# RHD2164_USBC.net
KiCad netlist of a schematic drawn in Altium Designer
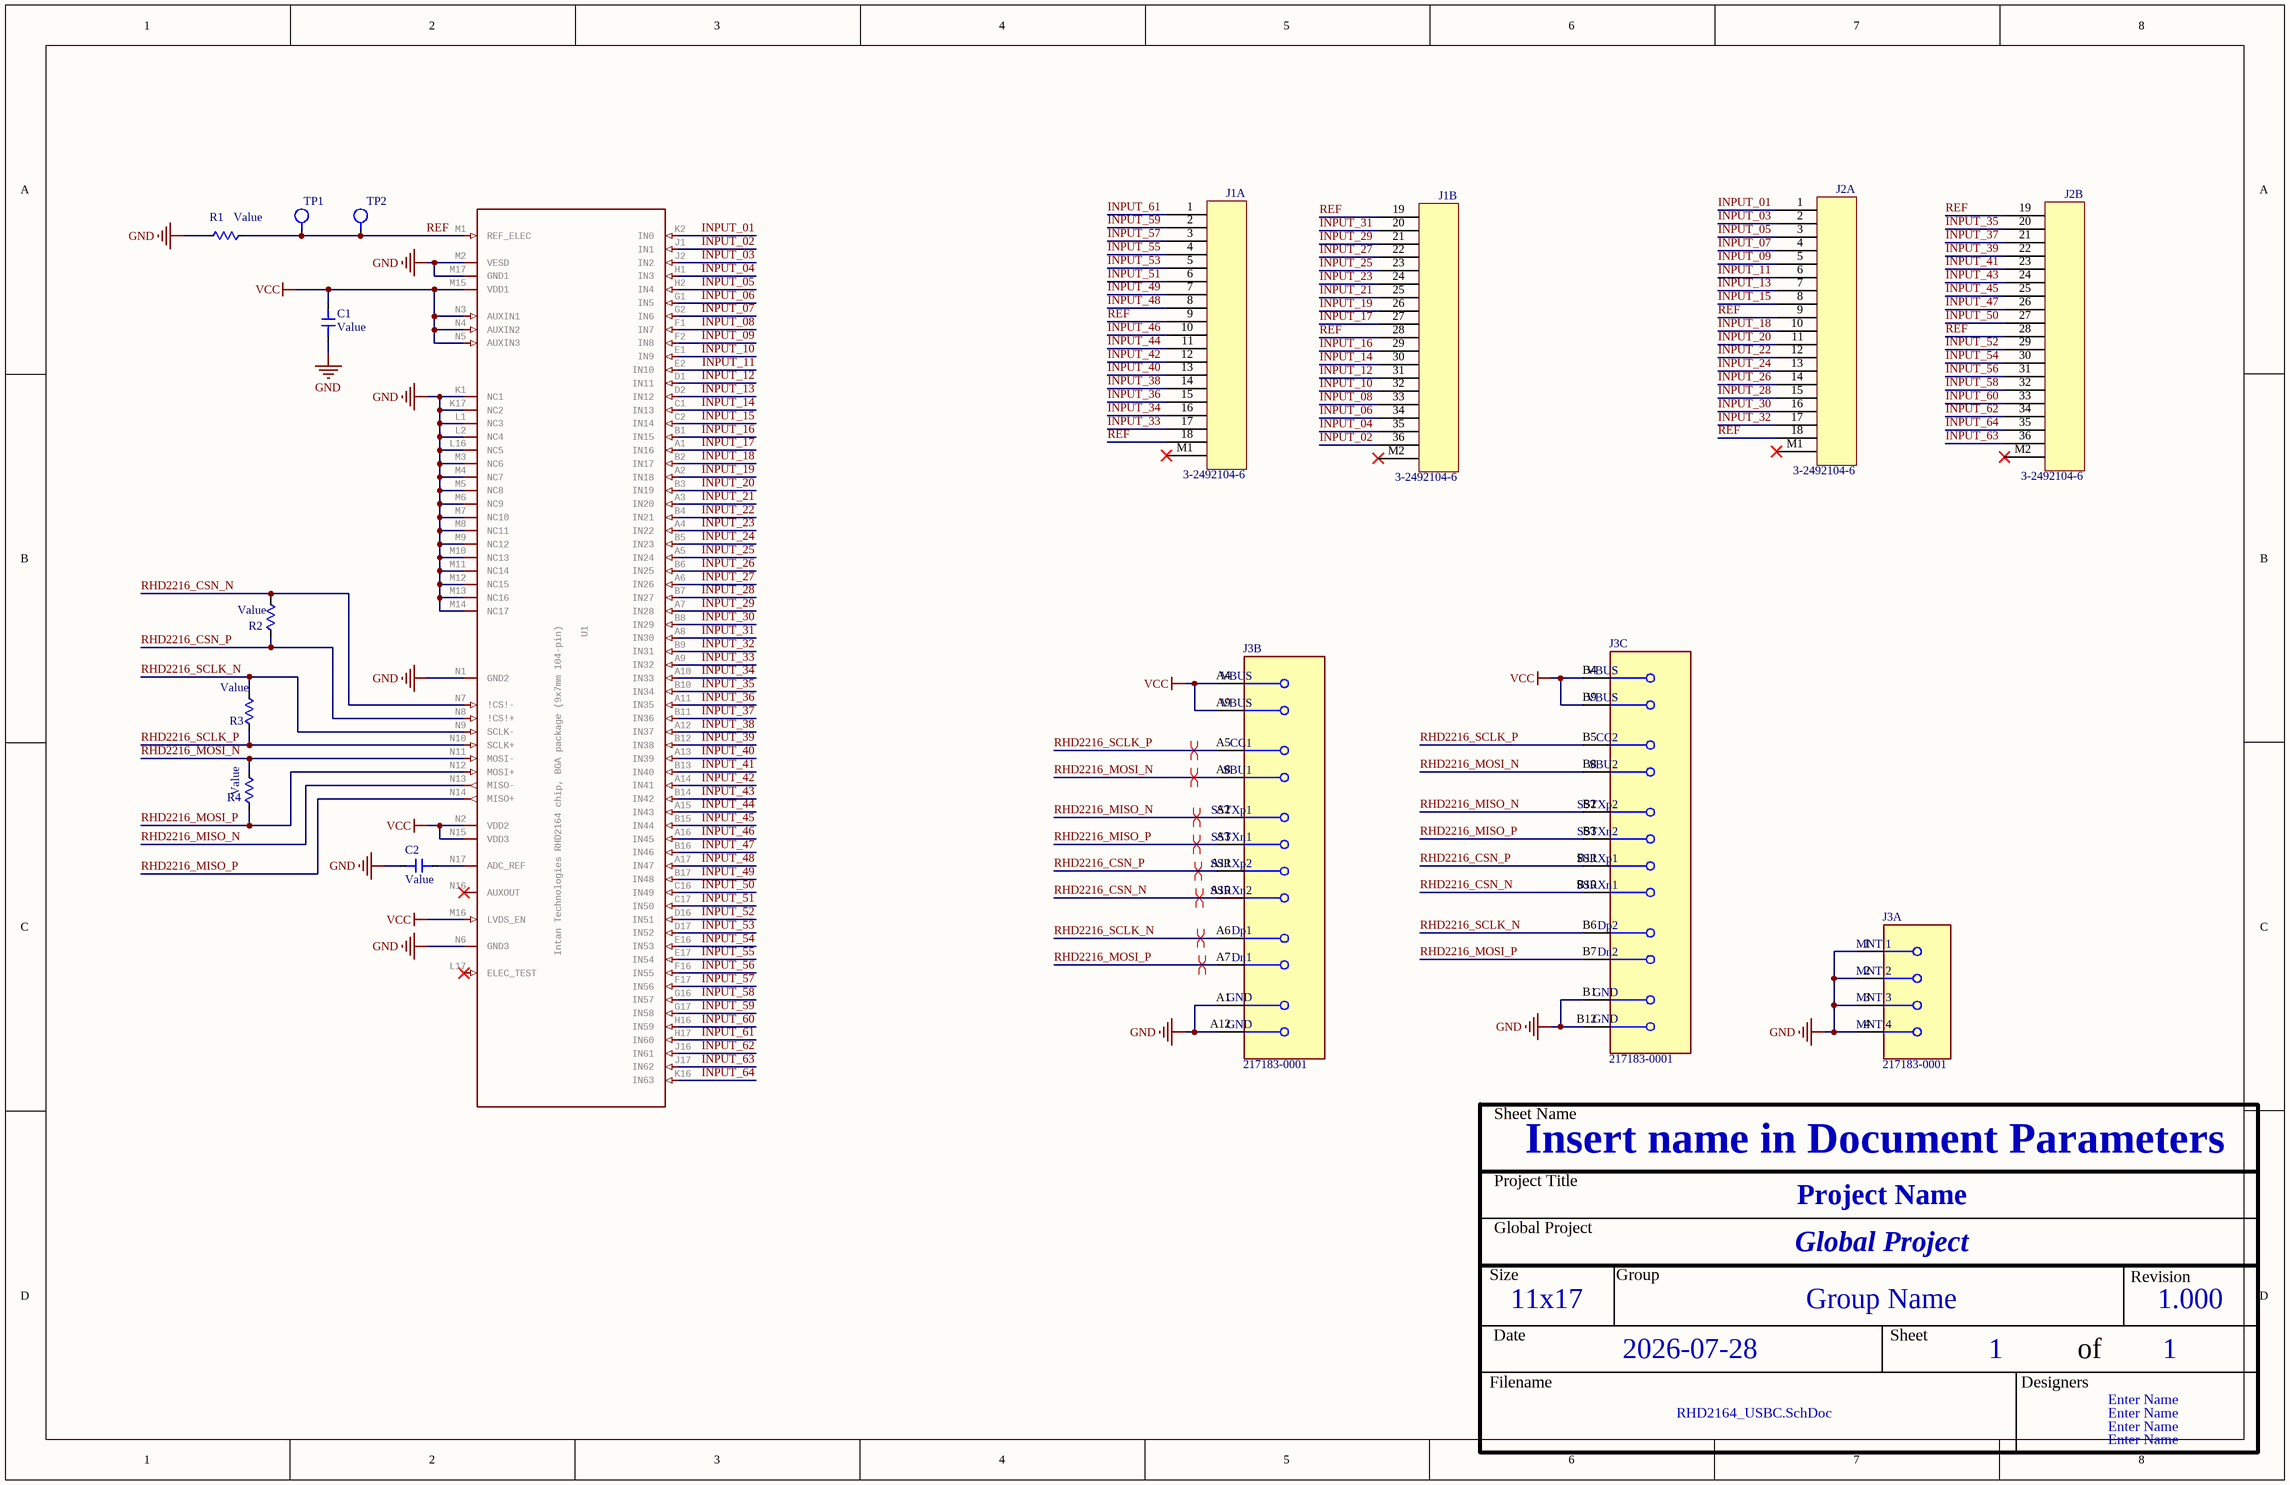
[diagram p0: RHD2164_USBC.SchDoc]

(export (version "E")
  (design (tool "Eeschema 10.0.6"))
  (components
    (comp (ref "C1")
      (value "Value")
      (footprint "0402_CAPACITOR")
      (description "Capacitor")
      (libsource (lib "RHD2164_USBC_V2") (part "Capacitor"))
    )
    (comp (ref "C2")
      (value "Value")
      (footprint "0402_CAPACITOR")
      (description "Capacitor")
      (libsource (lib "RHD2164_USBC_V2") (part "Capacitor"))
    )
    (comp (ref "J1")
      (value "3-2492104-6")
      (footprint "CON_ZIF_RA_36POS")
      (description "36 Position FPC Connector Contacts, Bottom 0.020\" (0.50mm) Surface Mount, Right Angle")
      (libsource (lib "RHD2164_USBC_V2") (part "CON_ZIF_RA_36POS"))
    )
    (comp (ref "J2")
      (value "3-2492104-6")
      (footprint "CON_ZIF_RA_36POS")
      (description "36 Position FPC Connector Contacts, Bottom 0.020\" (0.50mm) Surface Mount, Right Angle")
      (libsource (lib "RHD2164_USBC_V2") (part "CON_ZIF_RA_36POS"))
    )
    (comp (ref "J3")
      (value "217183-0001")
      (footprint "FP-217183-0001-MFG")
      (libsource (lib "Connectors") (part "CON_USBC_TH_SMT"))
    )
    (comp (ref "R1")
      (value "Value")
      (footprint "0402_Resistor")
      (description "Resistor")
      (libsource (lib "RHD2164_USBC_V2") (part "Resistor"))
    )
    (comp (ref "R2")
      (value "Value")
      (footprint "0402_Resistor")
      (description "Resistor")
      (libsource (lib "RHD2164_USBC_V2") (part "Resistor"))
    )
    (comp (ref "R3")
      (value "Value")
      (footprint "0402_Resistor")
      (description "Resistor")
      (libsource (lib "RHD2164_USBC_V2") (part "Resistor"))
    )
    (comp (ref "R4")
      (value "Value")
      (footprint "0402_Resistor")
      (description "Resistor")
      (libsource (lib "RHD2164_USBC_V2") (part "Resistor"))
    )
    (comp (ref "TP1")
      (value "TP_Small")
      (footprint "TP_Small_M2")
      (libsource (lib "RHD2164_USBC_V2") (part "TP_Small"))
    )
    (comp (ref "TP2")
      (value "TP_Small")
      (footprint "TP_Small_M2")
      (libsource (lib "RHD2164_USBC_V2") (part "TP_Small"))
    )
    (comp (ref "U1")
      (value "Intan Technologies RHD2164 chip, BGA package (9x7mm 104-pin)")
      (footprint "RHD2164_BGA")
      (libsource (lib "RHD2164_USBC_V2") (part "RHD2164_BGA_BGA"))
    )
  )
  (nets
    (net (code "1") (name "/INPUT_01") (class "Default")
      (node (ref "J2") (pin "1") (pinfunction "1_1") (pintype "passive"))
      (node (ref "U1") (pin "K2") (pinfunction "IN0_K2") (pintype "input"))
    )
    (net (code "2") (name "/INPUT_02") (class "Default")
      (node (ref "J1") (pin "36") (pinfunction "36_36") (pintype "passive"))
      (node (ref "U1") (pin "J1") (pinfunction "IN1_J1") (pintype "input"))
    )
    (net (code "3") (name "/INPUT_03") (class "Default")
      (node (ref "J2") (pin "2") (pinfunction "2_2") (pintype "passive"))
      (node (ref "U1") (pin "J2") (pinfunction "IN2_J2") (pintype "input"))
    )
    (net (code "4") (name "/INPUT_04") (class "Default")
      (node (ref "J1") (pin "35") (pinfunction "35_35") (pintype "passive"))
      (node (ref "U1") (pin "H1") (pinfunction "IN3_H1") (pintype "input"))
    )
    (net (code "5") (name "/INPUT_05") (class "Default")
      (node (ref "J2") (pin "3") (pinfunction "3_3") (pintype "passive"))
      (node (ref "U1") (pin "H2") (pinfunction "IN4_H2") (pintype "input"))
    )
    (net (code "6") (name "/INPUT_06") (class "Default")
      (node (ref "J1") (pin "34") (pinfunction "34_34") (pintype "passive"))
      (node (ref "U1") (pin "G1") (pinfunction "IN5_G1") (pintype "input"))
    )
    (net (code "7") (name "/INPUT_07") (class "Default")
      (node (ref "J2") (pin "4") (pinfunction "4_4") (pintype "passive"))
      (node (ref "U1") (pin "G2") (pinfunction "IN6_G2") (pintype "input"))
    )
    (net (code "8") (name "/INPUT_08") (class "Default")
      (node (ref "J1") (pin "33") (pinfunction "33_33") (pintype "passive"))
      (node (ref "U1") (pin "F1") (pinfunction "IN7_F1") (pintype "input"))
    )
    (net (code "9") (name "/INPUT_09") (class "Default")
      (node (ref "J2") (pin "5") (pinfunction "5_5") (pintype "passive"))
      (node (ref "U1") (pin "F2") (pinfunction "IN8_F2") (pintype "input"))
    )
    (net (code "10") (name "/INPUT_10") (class "Default")
      (node (ref "J1") (pin "32") (pinfunction "32_32") (pintype "passive"))
      (node (ref "U1") (pin "E1") (pinfunction "IN9_E1") (pintype "input"))
    )
    (net (code "11") (name "/INPUT_11") (class "Default")
      (node (ref "J2") (pin "6") (pinfunction "6_6") (pintype "passive"))
      (node (ref "U1") (pin "E2") (pinfunction "IN10_E2") (pintype "input"))
    )
    (net (code "12") (name "/INPUT_12") (class "Default")
      (node (ref "J1") (pin "31") (pinfunction "31_31") (pintype "passive"))
      (node (ref "U1") (pin "D1") (pinfunction "IN11_D1") (pintype "input"))
    )
    (net (code "13") (name "/INPUT_13") (class "Default")
      (node (ref "J2") (pin "7") (pinfunction "7_7") (pintype "passive"))
      (node (ref "U1") (pin "D2") (pinfunction "IN12_D2") (pintype "input"))
    )
    (net (code "14") (name "/INPUT_14") (class "Default")
      (node (ref "J1") (pin "30") (pinfunction "30_30") (pintype "passive"))
      (node (ref "U1") (pin "C1") (pinfunction "IN13_C1") (pintype "input"))
    )
    (net (code "15") (name "/INPUT_15") (class "Default")
      (node (ref "J2") (pin "8") (pinfunction "8_8") (pintype "passive"))
      (node (ref "U1") (pin "C2") (pinfunction "IN14_C2") (pintype "input"))
    )
    (net (code "16") (name "/INPUT_16") (class "Default")
      (node (ref "J1") (pin "29") (pinfunction "29_29") (pintype "passive"))
      (node (ref "U1") (pin "B1") (pinfunction "IN15_B1") (pintype "input"))
    )
    (net (code "17") (name "/INPUT_17") (class "Default")
      (node (ref "J1") (pin "27") (pinfunction "27_27") (pintype "passive"))
      (node (ref "U1") (pin "A1") (pinfunction "IN16_A1") (pintype "input"))
    )
    (net (code "18") (name "/INPUT_18") (class "Default")
      (node (ref "J2") (pin "10") (pinfunction "10_10") (pintype "passive"))
      (node (ref "U1") (pin "B2") (pinfunction "IN17_B2") (pintype "input"))
    )
    (net (code "19") (name "/INPUT_19") (class "Default")
      (node (ref "J1") (pin "26") (pinfunction "26_26") (pintype "passive"))
      (node (ref "U1") (pin "A2") (pinfunction "IN18_A2") (pintype "input"))
    )
    (net (code "20") (name "/INPUT_20") (class "Default")
      (node (ref "J2") (pin "11") (pinfunction "11_11") (pintype "passive"))
      (node (ref "U1") (pin "B3") (pinfunction "IN19_B3") (pintype "input"))
    )
    (net (code "21") (name "/INPUT_21") (class "Default")
      (node (ref "J1") (pin "25") (pinfunction "25_25") (pintype "passive"))
      (node (ref "U1") (pin "A3") (pinfunction "IN20_A3") (pintype "input"))
    )
    (net (code "22") (name "/INPUT_22") (class "Default")
      (node (ref "J2") (pin "12") (pinfunction "12_12") (pintype "passive"))
      (node (ref "U1") (pin "B4") (pinfunction "IN21_B4") (pintype "input"))
    )
    (net (code "23") (name "/INPUT_23") (class "Default")
      (node (ref "J1") (pin "24") (pinfunction "24_24") (pintype "passive"))
      (node (ref "U1") (pin "A4") (pinfunction "IN22_A4") (pintype "input"))
    )
    (net (code "24") (name "/INPUT_24") (class "Default")
      (node (ref "J2") (pin "13") (pinfunction "13_13") (pintype "passive"))
      (node (ref "U1") (pin "B5") (pinfunction "IN23_B5") (pintype "input"))
    )
    (net (code "25") (name "/INPUT_25") (class "Default")
      (node (ref "J1") (pin "23") (pinfunction "23_23") (pintype "passive"))
      (node (ref "U1") (pin "A5") (pinfunction "IN24_A5") (pintype "input"))
    )
    (net (code "26") (name "/INPUT_26") (class "Default")
      (node (ref "J2") (pin "14") (pinfunction "14_14") (pintype "passive"))
      (node (ref "U1") (pin "B6") (pinfunction "IN25_B6") (pintype "input"))
    )
    (net (code "27") (name "/INPUT_27") (class "Default")
      (node (ref "J1") (pin "22") (pinfunction "22_22") (pintype "passive"))
      (node (ref "U1") (pin "A6") (pinfunction "IN26_A6") (pintype "input"))
    )
    (net (code "28") (name "/INPUT_28") (class "Default")
      (node (ref "J2") (pin "15") (pinfunction "15_15") (pintype "passive"))
      (node (ref "U1") (pin "B7") (pinfunction "IN27_B7") (pintype "input"))
    )
    (net (code "29") (name "/INPUT_29") (class "Default")
      (node (ref "J1") (pin "21") (pinfunction "21_21") (pintype "passive"))
      (node (ref "U1") (pin "A7") (pinfunction "IN28_A7") (pintype "input"))
    )
    (net (code "30") (name "/INPUT_30") (class "Default")
      (node (ref "J2") (pin "16") (pinfunction "16_16") (pintype "passive"))
      (node (ref "U1") (pin "B8") (pinfunction "IN29_B8") (pintype "input"))
    )
    (net (code "31") (name "/INPUT_31") (class "Default")
      (node (ref "J1") (pin "20") (pinfunction "20_20") (pintype "passive"))
      (node (ref "U1") (pin "A8") (pinfunction "IN30_A8") (pintype "input"))
    )
    (net (code "32") (name "/INPUT_32") (class "Default")
      (node (ref "J2") (pin "17") (pinfunction "17_17") (pintype "passive"))
      (node (ref "U1") (pin "B9") (pinfunction "IN31_B9") (pintype "input"))
    )
    (net (code "33") (name "/INPUT_33") (class "Default")
      (node (ref "J1") (pin "17") (pinfunction "17_17") (pintype "passive"))
      (node (ref "U1") (pin "A9") (pinfunction "IN32_A9") (pintype "input"))
    )
    (net (code "34") (name "/INPUT_34") (class "Default")
      (node (ref "J1") (pin "16") (pinfunction "16_16") (pintype "passive"))
      (node (ref "U1") (pin "A10") (pinfunction "IN33_A10") (pintype "input"))
    )
    (net (code "35") (name "/INPUT_35") (class "Default")
      (node (ref "J2") (pin "20") (pinfunction "20_20") (pintype "passive"))
      (node (ref "U1") (pin "B10") (pinfunction "IN34_B10") (pintype "input"))
    )
    (net (code "36") (name "/INPUT_36") (class "Default")
      (node (ref "J1") (pin "15") (pinfunction "15_15") (pintype "passive"))
      (node (ref "U1") (pin "A11") (pinfunction "IN35_A11") (pintype "input"))
    )
    (net (code "37") (name "/INPUT_37") (class "Default")
      (node (ref "J2") (pin "21") (pinfunction "21_21") (pintype "passive"))
      (node (ref "U1") (pin "B11") (pinfunction "IN36_B11") (pintype "input"))
    )
    (net (code "38") (name "/INPUT_38") (class "Default")
      (node (ref "J1") (pin "14") (pinfunction "14_14") (pintype "passive"))
      (node (ref "U1") (pin "A12") (pinfunction "IN37_A12") (pintype "input"))
    )
    (net (code "39") (name "/INPUT_39") (class "Default")
      (node (ref "J2") (pin "22") (pinfunction "22_22") (pintype "passive"))
      (node (ref "U1") (pin "B12") (pinfunction "IN38_B12") (pintype "input"))
    )
    (net (code "40") (name "/INPUT_40") (class "Default")
      (node (ref "J1") (pin "13") (pinfunction "13_13") (pintype "passive"))
      (node (ref "U1") (pin "A13") (pinfunction "IN39_A13") (pintype "input"))
    )
    (net (code "41") (name "/INPUT_41") (class "Default")
      (node (ref "J2") (pin "23") (pinfunction "23_23") (pintype "passive"))
      (node (ref "U1") (pin "B13") (pinfunction "IN40_B13") (pintype "input"))
    )
    (net (code "42") (name "/INPUT_42") (class "Default")
      (node (ref "J1") (pin "12") (pinfunction "12_12") (pintype "passive"))
      (node (ref "U1") (pin "A14") (pinfunction "IN41_A14") (pintype "input"))
    )
    (net (code "43") (name "/INPUT_43") (class "Default")
      (node (ref "J2") (pin "24") (pinfunction "24_24") (pintype "passive"))
      (node (ref "U1") (pin "B14") (pinfunction "IN42_B14") (pintype "input"))
    )
    (net (code "44") (name "/INPUT_44") (class "Default")
      (node (ref "J1") (pin "11") (pinfunction "11_11") (pintype "passive"))
      (node (ref "U1") (pin "A15") (pinfunction "IN43_A15") (pintype "input"))
    )
    (net (code "45") (name "/INPUT_45") (class "Default")
      (node (ref "J2") (pin "25") (pinfunction "25_25") (pintype "passive"))
      (node (ref "U1") (pin "B15") (pinfunction "IN44_B15") (pintype "input"))
    )
    (net (code "46") (name "/INPUT_46") (class "Default")
      (node (ref "J1") (pin "10") (pinfunction "10_10") (pintype "passive"))
      (node (ref "U1") (pin "A16") (pinfunction "IN45_A16") (pintype "input"))
    )
    (net (code "47") (name "/INPUT_47") (class "Default")
      (node (ref "J2") (pin "26") (pinfunction "26_26") (pintype "passive"))
      (node (ref "U1") (pin "B16") (pinfunction "IN46_B16") (pintype "input"))
    )
    (net (code "48") (name "/INPUT_48") (class "Default")
      (node (ref "J1") (pin "8") (pinfunction "8_8") (pintype "passive"))
      (node (ref "U1") (pin "A17") (pinfunction "IN47_A17") (pintype "input"))
    )
    (net (code "49") (name "/INPUT_49") (class "Default")
      (node (ref "J1") (pin "7") (pinfunction "7_7") (pintype "passive"))
      (node (ref "U1") (pin "B17") (pinfunction "IN48_B17") (pintype "input"))
    )
    (net (code "50") (name "/INPUT_50") (class "Default")
      (node (ref "J2") (pin "27") (pinfunction "27_27") (pintype "passive"))
      (node (ref "U1") (pin "C16") (pinfunction "IN49_C16") (pintype "input"))
    )
    (net (code "51") (name "/INPUT_51") (class "Default")
      (node (ref "J1") (pin "6") (pinfunction "6_6") (pintype "passive"))
      (node (ref "U1") (pin "C17") (pinfunction "IN50_C17") (pintype "input"))
    )
    (net (code "52") (name "/INPUT_52") (class "Default")
      (node (ref "J2") (pin "29") (pinfunction "29_29") (pintype "passive"))
      (node (ref "U1") (pin "D16") (pinfunction "IN51_D16") (pintype "input"))
    )
    (net (code "53") (name "/INPUT_53") (class "Default")
      (node (ref "J1") (pin "5") (pinfunction "5_5") (pintype "passive"))
      (node (ref "U1") (pin "D17") (pinfunction "IN52_D17") (pintype "input"))
    )
    (net (code "54") (name "/INPUT_54") (class "Default")
      (node (ref "J2") (pin "30") (pinfunction "30_30") (pintype "passive"))
      (node (ref "U1") (pin "E16") (pinfunction "IN53_E16") (pintype "input"))
    )
    (net (code "55") (name "/INPUT_55") (class "Default")
      (node (ref "J1") (pin "4") (pinfunction "4_4") (pintype "passive"))
      (node (ref "U1") (pin "E17") (pinfunction "IN54_E17") (pintype "input"))
    )
    (net (code "56") (name "/INPUT_56") (class "Default")
      (node (ref "J2") (pin "31") (pinfunction "31_31") (pintype "passive"))
      (node (ref "U1") (pin "F16") (pinfunction "IN55_F16") (pintype "input"))
    )
    (net (code "57") (name "/INPUT_57") (class "Default")
      (node (ref "J1") (pin "3") (pinfunction "3_3") (pintype "passive"))
      (node (ref "U1") (pin "F17") (pinfunction "IN56_F17") (pintype "input"))
    )
    (net (code "58") (name "/INPUT_58") (class "Default")
      (node (ref "J2") (pin "32") (pinfunction "32_32") (pintype "passive"))
      (node (ref "U1") (pin "G16") (pinfunction "IN57_G16") (pintype "input"))
    )
    (net (code "59") (name "/INPUT_59") (class "Default")
      (node (ref "J1") (pin "2") (pinfunction "2_2") (pintype "passive"))
      (node (ref "U1") (pin "G17") (pinfunction "IN58_G17") (pintype "input"))
    )
    (net (code "60") (name "/INPUT_60") (class "Default")
      (node (ref "J2") (pin "33") (pinfunction "33_33") (pintype "passive"))
      (node (ref "U1") (pin "H16") (pinfunction "IN59_H16") (pintype "input"))
    )
    (net (code "61") (name "/INPUT_61") (class "Default")
      (node (ref "J1") (pin "1") (pinfunction "1_1") (pintype "passive"))
      (node (ref "U1") (pin "H17") (pinfunction "IN60_H17") (pintype "input"))
    )
    (net (code "62") (name "/INPUT_62") (class "Default")
      (node (ref "J2") (pin "34") (pinfunction "34_34") (pintype "passive"))
      (node (ref "U1") (pin "J16") (pinfunction "IN61_J16") (pintype "input"))
    )
    (net (code "63") (name "/INPUT_63") (class "Default")
      (node (ref "J2") (pin "36") (pinfunction "36_36") (pintype "passive"))
      (node (ref "U1") (pin "J17") (pinfunction "IN62_J17") (pintype "input"))
    )
    (net (code "64") (name "/INPUT_64") (class "Default")
      (node (ref "J2") (pin "35") (pinfunction "35_35") (pintype "passive"))
      (node (ref "U1") (pin "K16") (pinfunction "IN63_K16") (pintype "input"))
    )
    (net (code "65") (name "/REF") (class "Default")
      (node (ref "J1") (pin "18") (pinfunction "18_18") (pintype "passive"))
      (node (ref "J1") (pin "19") (pinfunction "19_19") (pintype "passive"))
      (node (ref "J1") (pin "28") (pinfunction "28_28") (pintype "passive"))
      (node (ref "J1") (pin "9") (pinfunction "9_9") (pintype "passive"))
      (node (ref "J2") (pin "18") (pinfunction "18_18") (pintype "passive"))
      (node (ref "J2") (pin "19") (pinfunction "19_19") (pintype "passive"))
      (node (ref "J2") (pin "28") (pinfunction "28_28") (pintype "passive"))
      (node (ref "J2") (pin "9") (pinfunction "9_9") (pintype "passive"))
      (node (ref "R1") (pin "2") (pinfunction "2_2") (pintype "passive"))
      (node (ref "TP1") (pin "1") (pinfunction "1_1") (pintype "passive"))
      (node (ref "TP2") (pin "1") (pinfunction "1_1") (pintype "passive"))
      (node (ref "U1") (pin "M1") (pinfunction "REF_ELEC_M1") (pintype "input"))
    )
    (net (code "66") (name "/RHD2216_CSN_N") (class "Default")
      (node (ref "J3") (pin "A10") (pinfunction "SSRXn2_A10") (pintype "passive"))
      (node (ref "J3") (pin "B10") (pinfunction "SSRXn1_B10") (pintype "passive"))
      (node (ref "R2") (pin "2") (pinfunction "2_2") (pintype "passive"))
      (node (ref "U1") (pin "N7") (pinfunction "!CS!-_N7") (pintype "input"))
    )
    (net (code "67") (name "/RHD2216_CSN_P") (class "Default")
      (node (ref "J3") (pin "A11") (pinfunction "SSRXp2_A11") (pintype "passive"))
      (node (ref "J3") (pin "B11") (pinfunction "SSRXp1_B11") (pintype "passive"))
      (node (ref "R2") (pin "1") (pinfunction "1_1") (pintype "passive"))
      (node (ref "U1") (pin "N8") (pinfunction "!CS!+_N8") (pintype "input"))
    )
    (net (code "68") (name "/RHD2216_MISO_N") (class "Default")
      (node (ref "J3") (pin "A2") (pinfunction "SSTXp1_A2") (pintype "passive"))
      (node (ref "J3") (pin "B2") (pinfunction "SSTXp2_B2") (pintype "passive"))
      (node (ref "U1") (pin "N13") (pinfunction "MISO-_N13") (pintype "output"))
    )
    (net (code "69") (name "/RHD2216_MISO_P") (class "Default")
      (node (ref "J3") (pin "A3") (pinfunction "SSTXn1_A3") (pintype "passive"))
      (node (ref "J3") (pin "B3") (pinfunction "SSTXn2_B3") (pintype "passive"))
      (node (ref "U1") (pin "N14") (pinfunction "MISO+_N14") (pintype "output"))
    )
    (net (code "70") (name "/RHD2216_MOSI_N") (class "Default")
      (node (ref "J3") (pin "A8") (pinfunction "SBU1_A8") (pintype "passive"))
      (node (ref "J3") (pin "B8") (pinfunction "SBU2_B8") (pintype "passive"))
      (node (ref "R4") (pin "2") (pinfunction "2_2") (pintype "passive"))
      (node (ref "U1") (pin "N11") (pinfunction "MOSI-_N11") (pintype "input"))
    )
    (net (code "71") (name "/RHD2216_MOSI_P") (class "Default")
      (node (ref "J3") (pin "A7") (pinfunction "Dn1_A7") (pintype "passive"))
      (node (ref "J3") (pin "B7") (pinfunction "Dn2_B7") (pintype "passive"))
      (node (ref "R4") (pin "1") (pinfunction "1_1") (pintype "passive"))
      (node (ref "U1") (pin "N12") (pinfunction "MOSI+_N12") (pintype "input"))
    )
    (net (code "72") (name "/RHD2216_SCLK_N") (class "Default")
      (node (ref "J3") (pin "A6") (pinfunction "Dp1_A6") (pintype "passive"))
      (node (ref "J3") (pin "B6") (pinfunction "Dp2_B6") (pintype "passive"))
      (node (ref "R3") (pin "2") (pinfunction "2_2") (pintype "passive"))
      (node (ref "U1") (pin "N9") (pinfunction "SCLK-_N9") (pintype "input"))
    )
    (net (code "73") (name "/RHD2216_SCLK_P") (class "Default")
      (node (ref "J3") (pin "A5") (pinfunction "CC1_A5") (pintype "passive"))
      (node (ref "J3") (pin "B5") (pinfunction "CC2_B5") (pintype "passive"))
      (node (ref "R3") (pin "1") (pinfunction "1_1") (pintype "passive"))
      (node (ref "U1") (pin "N10") (pinfunction "SCLK+_N10") (pintype "input"))
    )
    (net (code "74") (name "GND") (class "Default")
      (node (ref "C1") (pin "1") (pinfunction "1_1") (pintype "passive"))
      (node (ref "C2") (pin "2") (pinfunction "2_2") (pintype "passive"))
      (node (ref "J3") (pin "1") (pinfunction "MNT_1_1") (pintype "passive"))
      (node (ref "J3") (pin "2") (pinfunction "MNT_2_2") (pintype "passive"))
      (node (ref "J3") (pin "3") (pinfunction "MNT_3_3") (pintype "passive"))
      (node (ref "J3") (pin "4") (pinfunction "MNT_4_4") (pintype "passive"))
      (node (ref "J3") (pin "A1") (pinfunction "GND_A1") (pintype "passive"))
      (node (ref "J3") (pin "A12") (pinfunction "GND_A12") (pintype "passive"))
      (node (ref "J3") (pin "B1") (pinfunction "GND_B1") (pintype "passive"))
      (node (ref "J3") (pin "B12") (pinfunction "GND_B12") (pintype "passive"))
      (node (ref "R1") (pin "1") (pinfunction "1_1") (pintype "passive"))
      (node (ref "U1") (pin "K1") (pinfunction "NC1_K1") (pintype "passive"))
      (node (ref "U1") (pin "K17") (pinfunction "NC2_K17") (pintype "passive"))
      (node (ref "U1") (pin "L1") (pinfunction "NC3_L1") (pintype "passive"))
      (node (ref "U1") (pin "L16") (pinfunction "NC5_L16") (pintype "passive"))
      (node (ref "U1") (pin "L2") (pinfunction "NC4_L2") (pintype "passive"))
      (node (ref "U1") (pin "M10") (pinfunction "NC13_M10") (pintype "passive"))
      (node (ref "U1") (pin "M11") (pinfunction "NC14_M11") (pintype "passive"))
      (node (ref "U1") (pin "M12") (pinfunction "NC15_M12") (pintype "passive"))
      (node (ref "U1") (pin "M13") (pinfunction "NC16_M13") (pintype "passive"))
      (node (ref "U1") (pin "M14") (pinfunction "NC17_M14") (pintype "passive"))
      (node (ref "U1") (pin "M17") (pinfunction "GND1_M17") (pintype "power_in"))
      (node (ref "U1") (pin "M2") (pinfunction "VESD_M2") (pintype "power_in"))
      (node (ref "U1") (pin "M3") (pinfunction "NC6_M3") (pintype "passive"))
      (node (ref "U1") (pin "M4") (pinfunction "NC7_M4") (pintype "passive"))
      (node (ref "U1") (pin "M5") (pinfunction "NC8_M5") (pintype "passive"))
      (node (ref "U1") (pin "M6") (pinfunction "NC9_M6") (pintype "passive"))
      (node (ref "U1") (pin "M7") (pinfunction "NC10_M7") (pintype "passive"))
      (node (ref "U1") (pin "M8") (pinfunction "NC11_M8") (pintype "passive"))
      (node (ref "U1") (pin "M9") (pinfunction "NC12_M9") (pintype "passive"))
      (node (ref "U1") (pin "N1") (pinfunction "GND2_N1") (pintype "power_in"))
      (node (ref "U1") (pin "N6") (pinfunction "GND3_N6") (pintype "power_in"))
    )
    (net (code "75") (name "Net-(U1-ADC_REF)") (class "Default")
      (node (ref "C2") (pin "1") (pinfunction "1_1") (pintype "passive"))
      (node (ref "U1") (pin "N17") (pinfunction "ADC_REF_N17") (pintype "passive"))
    )
    (net (code "76") (name "VCC") (class "Default")
      (node (ref "C1") (pin "2") (pinfunction "2_2") (pintype "passive"))
      (node (ref "J3") (pin "A4") (pinfunction "VBUS_A4") (pintype "passive"))
      (node (ref "J3") (pin "A9") (pinfunction "VBUS_A9") (pintype "passive"))
      (node (ref "J3") (pin "B4") (pinfunction "VBUS_B4") (pintype "passive"))
      (node (ref "J3") (pin "B9") (pinfunction "VBUS_B9") (pintype "passive"))
      (node (ref "U1") (pin "M15") (pinfunction "VDD1_M15") (pintype "power_in"))
      (node (ref "U1") (pin "M16") (pinfunction "LVDS_EN_M16") (pintype "input"))
      (node (ref "U1") (pin "N15") (pinfunction "VDD3_N15") (pintype "power_in"))
      (node (ref "U1") (pin "N2") (pinfunction "VDD2_N2") (pintype "power_in"))
      (node (ref "U1") (pin "N3") (pinfunction "AUXIN1_N3") (pintype "input"))
      (node (ref "U1") (pin "N4") (pinfunction "AUXIN2_N4") (pintype "input"))
      (node (ref "U1") (pin "N5") (pinfunction "AUXIN3_N5") (pintype "input"))
    )
    (net (code "77") (name "unconnected-(J1-PadM1)") (class "Default")
      (node (ref "J1") (pin "M1") (pinfunction "M1_M1") (pintype "passive+no_connect"))
    )
    (net (code "78") (name "unconnected-(J1-PadM2)") (class "Default")
      (node (ref "J1") (pin "M2") (pinfunction "M2_M2") (pintype "passive+no_connect"))
    )
    (net (code "79") (name "unconnected-(J2-PadM1)") (class "Default")
      (node (ref "J2") (pin "M1") (pinfunction "M1_M1") (pintype "passive+no_connect"))
    )
    (net (code "80") (name "unconnected-(J2-PadM2)") (class "Default")
      (node (ref "J2") (pin "M2") (pinfunction "M2_M2") (pintype "passive+no_connect"))
    )
    (net (code "81") (name "unconnected-(U1-AUXOUT-PadN16)") (class "Default")
      (node (ref "U1") (pin "N16") (pinfunction "AUXOUT_N16") (pintype "tri_state+no_connect"))
    )
    (net (code "82") (name "unconnected-(U1-ELEC_TEST-PadL17)") (class "Default")
      (node (ref "U1") (pin "L17") (pinfunction "ELEC_TEST_L17") (pintype "input+no_connect"))
    )
  )
)
